# revalarm.net
KiCad netlist of a schematic drawn in EAGLE
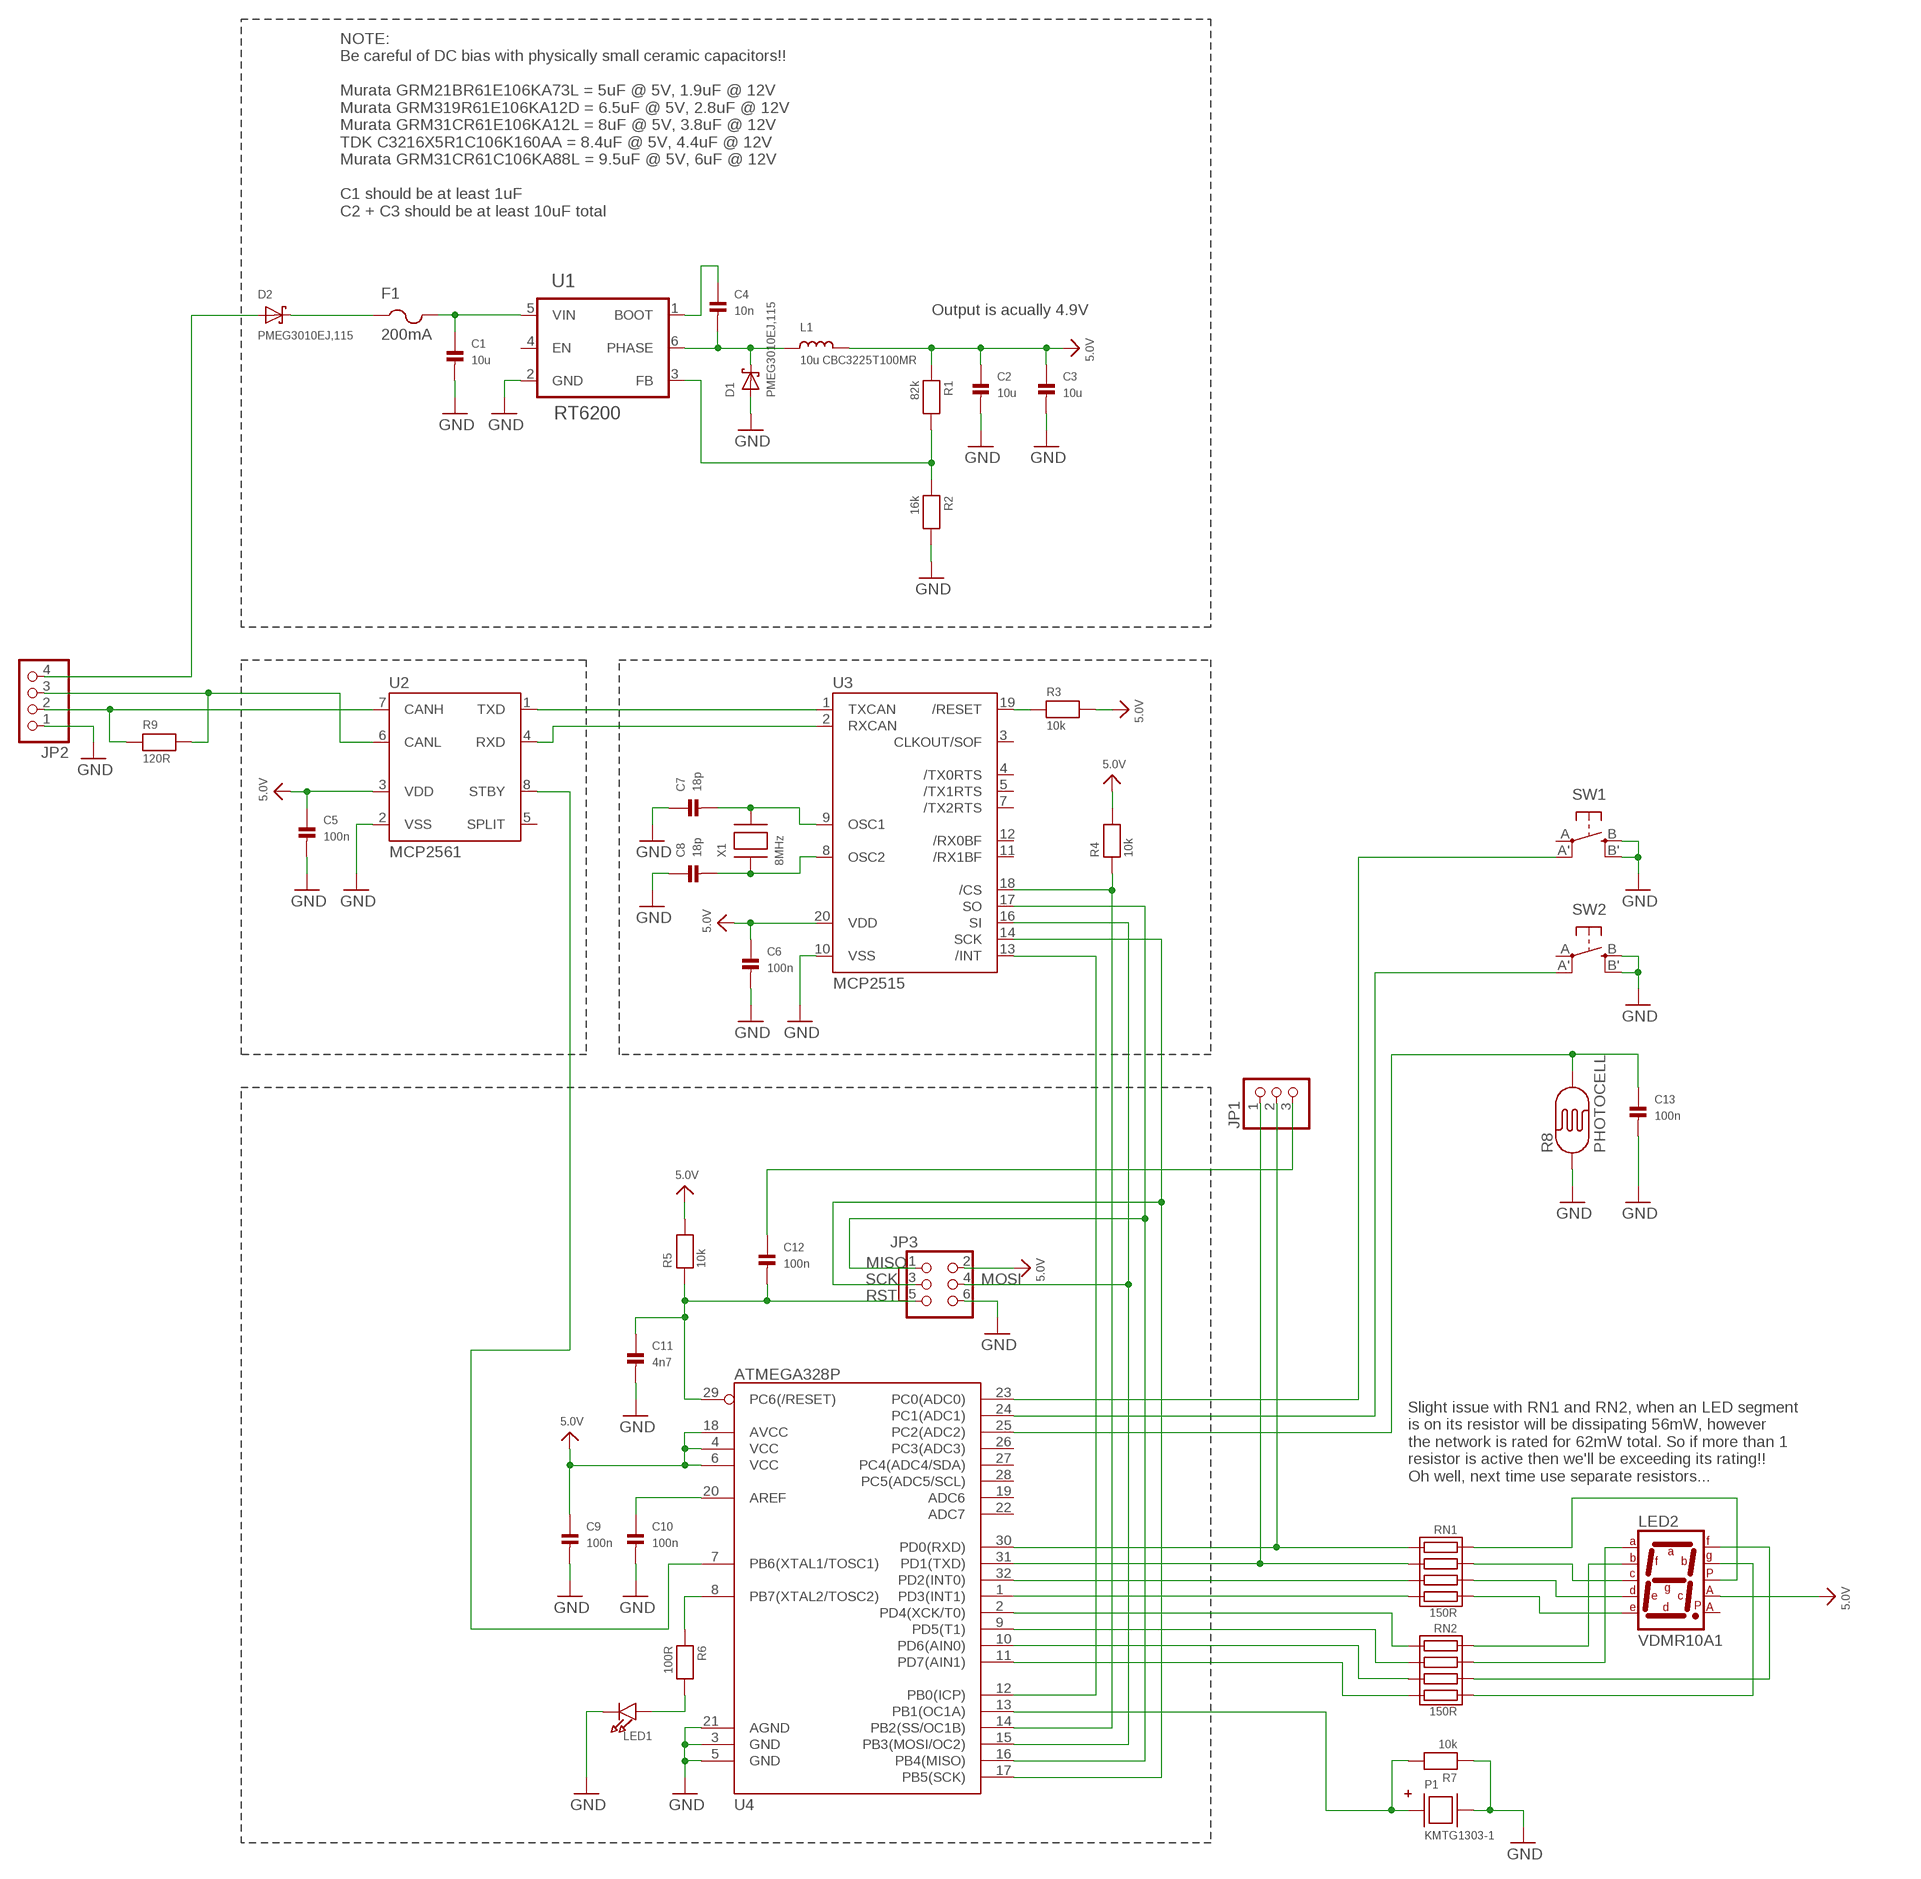
[diagram p0: schematic, sheet 1]

(export (version "E")
  (design (tool "Eeschema 10.0.6"))
  (components
    (comp (ref "C1")
      (value "10u")
      (footprint "eagle-import:1206")
      (libsource (lib "eagle-import") (part "CAP_CERAMIC1206"))
    )
    (comp (ref "C2")
      (value "10u")
      (footprint "eagle-import:1206")
      (libsource (lib "eagle-import") (part "CAP_CERAMIC1206"))
    )
    (comp (ref "C3")
      (value "10u")
      (footprint "eagle-import:1206")
      (libsource (lib "eagle-import") (part "CAP_CERAMIC1206"))
    )
    (comp (ref "C4")
      (value "10n")
      (footprint "eagle-import:0402")
      (libsource (lib "eagle-import") (part "CAP_CERAMIC0402"))
    )
    (comp (ref "C5")
      (value "100n")
      (footprint "eagle-import:0402")
      (libsource (lib "eagle-import") (part "CAP_CERAMIC0402"))
    )
    (comp (ref "C6")
      (value "100n")
      (footprint "eagle-import:0402")
      (libsource (lib "eagle-import") (part "CAP_CERAMIC0402"))
    )
    (comp (ref "C7")
      (value "18p")
      (footprint "eagle-import:0402")
      (libsource (lib "eagle-import") (part "CAP_CERAMIC0402"))
    )
    (comp (ref "C8")
      (value "18p")
      (footprint "eagle-import:0402")
      (libsource (lib "eagle-import") (part "CAP_CERAMIC0402"))
    )
    (comp (ref "C9")
      (value "100n")
      (footprint "eagle-import:0402")
      (libsource (lib "eagle-import") (part "CAP_CERAMIC0402"))
    )
    (comp (ref "C10")
      (value "100n")
      (footprint "eagle-import:0402")
      (libsource (lib "eagle-import") (part "CAP_CERAMIC0402"))
    )
    (comp (ref "C11")
      (value "4n7")
      (footprint "eagle-import:0402")
      (libsource (lib "eagle-import") (part "CAP_CERAMIC0402"))
    )
    (comp (ref "C12")
      (value "100n")
      (footprint "eagle-import:0402")
      (libsource (lib "eagle-import") (part "CAP_CERAMIC0402"))
    )
    (comp (ref "C13")
      (value "100n")
      (footprint "eagle-import:0402")
      (libsource (lib "eagle-import") (part "CAP_CERAMIC0402"))
    )
    (comp (ref "D1")
      (value "PMEG3010EJ,115")
      (footprint "eagle-import:SOD-323")
      (libsource (lib "eagle-import") (part "DIODE-SCHOTTKYSOD-323"))
    )
    (comp (ref "D2")
      (value "PMEG3010EJ,115")
      (footprint "eagle-import:SOD-323")
      (libsource (lib "eagle-import") (part "DIODE-SCHOTTKYSOD-323"))
    )
    (comp (ref "F1")
      (value "200mA")
      (footprint "eagle-import:1206")
      (libsource (lib "eagle-import") (part "PTCFUSE1206"))
    )
    (comp (ref "JP1")
      (value "PINHD-1X3")
      (footprint "eagle-import:1X03")
      (libsource (lib "eagle-import") (part "PINHD-1X3"))
    )
    (comp (ref "JP2")
      (value "PINHD-1X4")
      (footprint "eagle-import:1X04")
      (libsource (lib "eagle-import") (part "PINHD-1X4"))
    )
    (comp (ref "JP3")
      (value "ISP6PINPOGO_PIXELRGB")
      (footprint "eagle-import:POGO60PIN_PIXELRGB")
      (libsource (lib "eagle-import") (part "ISP6PINPOGO_PIXELRGB"))
    )
    (comp (ref "L1")
      (value "10u CBC3225T100MR")
      (footprint "eagle-import:1210K")
      (libsource (lib "eagle-import") (part "INDUCTOR1210K"))
    )
    (comp (ref "LED1")
      (value "LED0805_NOOUTLINE")
      (footprint "eagle-import:CHIPLED_0805_NOOUTLINE")
      (libsource (lib "eagle-import") (part "LED0805_NOOUTLINE"))
    )
    (comp (ref "LED2")
      (value "VDMR10A1")
      (footprint "eagle-import:7SEG-SMD")
      (libsource (lib "eagle-import") (part "7SEGVDMR10A1"))
    )
    (comp (ref "P1")
      (value "KMTG1303-1")
      (footprint "eagle-import:KMTG1303")
      (libsource (lib "eagle-import") (part "PIEZOKMTG1303"))
    )
    (comp (ref "R1")
      (value "82k")
      (footprint "eagle-import:0402")
      (libsource (lib "eagle-import") (part "RESISTOR0402"))
    )
    (comp (ref "R2")
      (value "16k")
      (footprint "eagle-import:0402")
      (libsource (lib "eagle-import") (part "RESISTOR0402"))
    )
    (comp (ref "R3")
      (value "10k")
      (footprint "eagle-import:0402")
      (libsource (lib "eagle-import") (part "RESISTOR0402"))
    )
    (comp (ref "R4")
      (value "10k")
      (footprint "eagle-import:0402")
      (libsource (lib "eagle-import") (part "RESISTOR0402"))
    )
    (comp (ref "R5")
      (value "10k")
      (footprint "eagle-import:0402")
      (libsource (lib "eagle-import") (part "RESISTOR0402"))
    )
    (comp (ref "R6")
      (value "100R")
      (footprint "eagle-import:0402")
      (libsource (lib "eagle-import") (part "RESISTOR0402"))
    )
    (comp (ref "R7")
      (value "10k")
      (footprint "eagle-import:0402")
      (libsource (lib "eagle-import") (part "RESISTOR0402"))
    )
    (comp (ref "R8")
      (value "PHOTOCELL")
      (footprint "eagle-import:PHOTOCELL")
      (libsource (lib "eagle-import") (part "PHOTOCELL"))
    )
    (comp (ref "R9")
      (value "120R")
      (footprint "eagle-import:1206")
      (libsource (lib "eagle-import") (part "RESISTOR1206"))
    )
    (comp (ref "RN1")
      (value "150R")
      (footprint "eagle-import:RESPACK_4X0603")
      (libsource (lib "eagle-import") (part "RESPACK_4STATIC"))
    )
    (comp (ref "RN2")
      (value "150R")
      (footprint "eagle-import:RESPACK_4X0603")
      (libsource (lib "eagle-import") (part "RESPACK_4STATIC"))
    )
    (comp (ref "SW1")
      (value "SPST_TACTMC32882")
      (footprint "eagle-import:TACT_SMD4")
      (libsource (lib "eagle-import") (part "SPST_TACTMC32882"))
    )
    (comp (ref "SW2")
      (value "SPST_TACTMC32882")
      (footprint "eagle-import:TACT_SMD4")
      (libsource (lib "eagle-import") (part "SPST_TACTMC32882"))
    )
    (comp (ref "U1")
      (value "RT6200")
      (footprint "eagle-import:SOT23-6_SM_PAD")
      (libsource (lib "eagle-import") (part "RT6200SOT-23-6"))
    )
    (comp (ref "U2")
      (value "MCP2561")
      (footprint "eagle-import:SOIC8_150MIL_SMPAD")
      (libsource (lib "eagle-import") (part "MCP2561"))
    )
    (comp (ref "U3")
      (value "MCP2515")
      (footprint "eagle-import:TSSOP20")
      (libsource (lib "eagle-import") (part "CANCONTROLLERTSSOP20"))
    )
    (comp (ref "U4")
      (value "ATMEGA328P")
      (footprint "eagle-import:TQFP32-08")
      (libsource (lib "eagle-import") (part "ATMEGA328_SMT"))
    )
    (comp (ref "X1")
      (value "8MHz")
      (footprint "eagle-import:NX5032")
      (libsource (lib "eagle-import") (part "XTALNX5032"))
    )
  )
  (nets
    (net (code "1") (name "/MISO") (class "Default")
      (node (ref "JP3") (pin "1") (pinfunction "1_1") (pintype "passive"))
      (node (ref "U3") (pin "17") (pinfunction "SO_17") (pintype "power_in"))
      (node (ref "U4") (pin "16") (pinfunction "PB4(MISO)_16") (pintype "bidirectional"))
    )
    (net (code "2") (name "/MOSI") (class "Default")
      (node (ref "JP3") (pin "4") (pinfunction "4_4") (pintype "passive"))
      (node (ref "U3") (pin "16") (pinfunction "SI_16") (pintype "passive"))
      (node (ref "U4") (pin "15") (pinfunction "PB3(MOSI/OC2)_15") (pintype "bidirectional"))
    )
    (net (code "3") (name "/RST") (class "Default")
      (node (ref "C11") (pin "1") (pinfunction "P$1_1") (pintype "passive"))
      (node (ref "C12") (pin "2") (pinfunction "P$2_2") (pintype "passive"))
      (node (ref "JP3") (pin "5") (pinfunction "5_5") (pintype "passive"))
      (node (ref "R5") (pin "1") (pinfunction "1_1") (pintype "passive"))
      (node (ref "U4") (pin "29") (pinfunction "PC6(/RESET)_29") (pintype "bidirectional"))
    )
    (net (code "4") (name "/SCK") (class "Default")
      (node (ref "JP3") (pin "3") (pinfunction "3_3") (pintype "passive"))
      (node (ref "U3") (pin "14") (pinfunction "SCK_14") (pintype "passive"))
      (node (ref "U4") (pin "17") (pinfunction "PB5(SCK)_17") (pintype "bidirectional"))
    )
    (net (code "5") (name "5.0V") (class "Default")
      (node (ref "C2") (pin "1") (pinfunction "P$1_1") (pintype "passive"))
      (node (ref "C3") (pin "1") (pinfunction "P$1_1") (pintype "passive"))
      (node (ref "C5") (pin "1") (pinfunction "P$1_1") (pintype "passive"))
      (node (ref "C6") (pin "1") (pinfunction "P$1_1") (pintype "passive"))
      (node (ref "C9") (pin "1") (pinfunction "P$1_1") (pintype "passive"))
      (node (ref "JP3") (pin "2") (pinfunction "2_2") (pintype "power_in"))
      (node (ref "L1") (pin "2") (pinfunction "2_2") (pintype "passive"))
      (node (ref "LED2") (pin "COMM1") (pinfunction "CA1_COMM1") (pintype "passive"))
      (node (ref "R1") (pin "1") (pinfunction "1_1") (pintype "passive"))
      (node (ref "R3") (pin "2") (pinfunction "2_2") (pintype "passive"))
      (node (ref "R4") (pin "2") (pinfunction "2_2") (pintype "passive"))
      (node (ref "R5") (pin "2") (pinfunction "2_2") (pintype "passive"))
      (node (ref "U2") (pin "3") (pinfunction "VDD_3") (pintype "passive"))
      (node (ref "U3") (pin "20") (pinfunction "VDD_20") (pintype "passive"))
      (node (ref "U4") (pin "18") (pinfunction "AVCC_18") (pintype "bidirectional"))
      (node (ref "U4") (pin "4") (pinfunction "VCC_4") (pintype "bidirectional"))
      (node (ref "U4") (pin "6") (pinfunction "VCC_6") (pintype "bidirectional"))
    )
    (net (code "6") (name "GND") (class "Default")
      (node (ref "C1") (pin "2") (pinfunction "P$2_2") (pintype "passive"))
      (node (ref "C10") (pin "2") (pinfunction "P$2_2") (pintype "passive"))
      (node (ref "C11") (pin "2") (pinfunction "P$2_2") (pintype "passive"))
      (node (ref "C13") (pin "2") (pinfunction "P$2_2") (pintype "passive"))
      (node (ref "C2") (pin "2") (pinfunction "P$2_2") (pintype "passive"))
      (node (ref "C3") (pin "2") (pinfunction "P$2_2") (pintype "passive"))
      (node (ref "C5") (pin "2") (pinfunction "P$2_2") (pintype "passive"))
      (node (ref "C6") (pin "2") (pinfunction "P$2_2") (pintype "passive"))
      (node (ref "C7") (pin "1") (pinfunction "P$1_1") (pintype "passive"))
      (node (ref "C8") (pin "1") (pinfunction "P$1_1") (pintype "passive"))
      (node (ref "C9") (pin "2") (pinfunction "P$2_2") (pintype "passive"))
      (node (ref "D1") (pin "A") (pinfunction "A_A") (pintype "passive"))
      (node (ref "JP2") (pin "1") (pinfunction "1_1") (pintype "passive"))
      (node (ref "JP3") (pin "6") (pinfunction "6_6") (pintype "passive"))
      (node (ref "LED1") (pin "C") (pinfunction "C_C") (pintype "passive"))
      (node (ref "P1") (pin "P$2") (pinfunction "GND_P$2") (pintype "passive"))
      (node (ref "R2") (pin "2") (pinfunction "2_2") (pintype "passive"))
      (node (ref "R7") (pin "1") (pinfunction "1_1") (pintype "passive"))
      (node (ref "R8") (pin "1") (pinfunction "P$1_1") (pintype "bidirectional"))
      (node (ref "SW1") (pin "B") (pinfunction "S_B") (pintype "passive"))
      (node (ref "SW1") (pin "B'") (pinfunction "S1_B'") (pintype "passive"))
      (node (ref "SW2") (pin "B") (pinfunction "S_B") (pintype "passive"))
      (node (ref "SW2") (pin "B'") (pinfunction "S1_B'") (pintype "passive"))
      (node (ref "U1") (pin "2") (pinfunction "GND_2") (pintype "passive"))
      (node (ref "U2") (pin "2") (pinfunction "VSS_2") (pintype "passive"))
      (node (ref "U3") (pin "10") (pinfunction "VSS_10") (pintype "passive"))
      (node (ref "U4") (pin "21") (pinfunction "AGND_21") (pintype "bidirectional"))
      (node (ref "U4") (pin "3") (pinfunction "GND_3") (pintype "bidirectional"))
      (node (ref "U4") (pin "5") (pinfunction "GND_5") (pintype "bidirectional"))
    )
    (net (code "7") (name "Net-(C1-P$1)") (class "Default")
      (node (ref "C1") (pin "1") (pinfunction "P$1_1") (pintype "passive"))
      (node (ref "F1") (pin "2") (pinfunction "2_2") (pintype "passive"))
      (node (ref "U1") (pin "5") (pinfunction "VIN_5") (pintype "input"))
    )
    (net (code "8") (name "Net-(C4-P$1)") (class "Default")
      (node (ref "C4") (pin "1") (pinfunction "P$1_1") (pintype "passive"))
      (node (ref "U1") (pin "1") (pinfunction "BOOT_1") (pintype "output"))
    )
    (net (code "9") (name "Net-(C4-P$2)") (class "Default")
      (node (ref "C4") (pin "2") (pinfunction "P$2_2") (pintype "passive"))
      (node (ref "D1") (pin "C") (pinfunction "C_C") (pintype "passive"))
      (node (ref "L1") (pin "1") (pinfunction "1_1") (pintype "passive"))
      (node (ref "U1") (pin "6") (pinfunction "PHASE_6") (pintype "output"))
    )
    (net (code "10") (name "Net-(C7-P$2)") (class "Default")
      (node (ref "C7") (pin "2") (pinfunction "P$2_2") (pintype "passive"))
      (node (ref "U3") (pin "9") (pinfunction "OSC1_9") (pintype "passive"))
      (node (ref "X1") (pin "P$2") (pinfunction "P$2_P$2") (pintype "bidirectional"))
    )
    (net (code "11") (name "Net-(C8-P$2)") (class "Default")
      (node (ref "C8") (pin "2") (pinfunction "P$2_2") (pintype "passive"))
      (node (ref "U3") (pin "8") (pinfunction "OSC2_8") (pintype "passive"))
      (node (ref "X1") (pin "P$1") (pinfunction "P$1_P$1") (pintype "bidirectional"))
    )
    (net (code "12") (name "Net-(C10-P$1)") (class "Default")
      (node (ref "C10") (pin "1") (pinfunction "P$1_1") (pintype "passive"))
      (node (ref "U4") (pin "20") (pinfunction "AREF_20") (pintype "bidirectional"))
    )
    (net (code "13") (name "Net-(C12-P$1)") (class "Default")
      (node (ref "C12") (pin "1") (pinfunction "P$1_1") (pintype "passive"))
      (node (ref "JP1") (pin "3") (pinfunction "3_3") (pintype "passive"))
    )
    (net (code "14") (name "Net-(C13-P$1)") (class "Default")
      (node (ref "C13") (pin "1") (pinfunction "P$1_1") (pintype "passive"))
      (node (ref "R8") (pin "2") (pinfunction "P$2_2") (pintype "bidirectional"))
      (node (ref "U4") (pin "25") (pinfunction "PC2(ADC2)_25") (pintype "bidirectional"))
    )
    (net (code "15") (name "Net-(D2-PadA)") (class "Default")
      (node (ref "D2") (pin "A") (pinfunction "A_A") (pintype "passive"))
      (node (ref "JP2") (pin "4") (pinfunction "4_4") (pintype "passive"))
    )
    (net (code "16") (name "Net-(D2-PadC)") (class "Default")
      (node (ref "D2") (pin "C") (pinfunction "C_C") (pintype "passive"))
      (node (ref "F1") (pin "1") (pinfunction "1_1") (pintype "passive"))
    )
    (net (code "17") (name "Net-(LED1-PadA)") (class "Default")
      (node (ref "LED1") (pin "A") (pinfunction "A_A") (pintype "passive"))
      (node (ref "R6") (pin "2") (pinfunction "2_2") (pintype "passive"))
    )
    (net (code "18") (name "Net-(LED2-PadB)") (class "Default")
      (node (ref "LED2") (pin "B") (pinfunction "B_B") (pintype "passive"))
      (node (ref "RN2") (pin "1") (pinfunction "1_1") (pintype "passive"))
    )
    (net (code "19") (name "Net-(LED2-PadDP)") (class "Default")
      (node (ref "LED2") (pin "DP") (pinfunction "DP_DP") (pintype "passive"))
      (node (ref "RN1") (pin "1") (pinfunction "1_1") (pintype "passive"))
    )
    (net (code "20") (name "Net-(P1-VCC)") (class "Default")
      (node (ref "P1") (pin "P$1") (pinfunction "VCC_P$1") (pintype "passive"))
      (node (ref "R7") (pin "2") (pinfunction "2_2") (pintype "passive"))
      (node (ref "U4") (pin "13") (pinfunction "PB1(OC1A)_13") (pintype "bidirectional"))
    )
    (net (code "21") (name "Net-(RN1-2)") (class "Default")
      (node (ref "JP1") (pin "2") (pinfunction "2_2") (pintype "passive"))
      (node (ref "RN1") (pin "8") (pinfunction "2_8") (pintype "passive"))
      (node (ref "U4") (pin "30") (pinfunction "PD0(RXD)_30") (pintype "bidirectional"))
    )
    (net (code "22") (name "Net-(RN1-3)") (class "Default")
      (node (ref "LED2") (pin "C") (pinfunction "C_C") (pintype "passive"))
      (node (ref "RN1") (pin "2") (pinfunction "3_2") (pintype "passive"))
    )
    (net (code "23") (name "Net-(RN1-4)") (class "Default")
      (node (ref "JP1") (pin "1") (pinfunction "1_1") (pintype "passive"))
      (node (ref "RN1") (pin "7") (pinfunction "4_7") (pintype "passive"))
      (node (ref "U4") (pin "31") (pinfunction "PD1(TXD)_31") (pintype "bidirectional"))
    )
    (net (code "24") (name "Net-(RN1-5)") (class "Default")
      (node (ref "LED2") (pin "D") (pinfunction "D_D") (pintype "passive"))
      (node (ref "RN1") (pin "3") (pinfunction "5_3") (pintype "passive"))
    )
    (net (code "25") (name "Net-(RN1-7)") (class "Default")
      (node (ref "LED2") (pin "E") (pinfunction "E_E") (pintype "passive"))
      (node (ref "RN1") (pin "4") (pinfunction "7_4") (pintype "passive"))
    )
    (net (code "26") (name "Net-(RN1-8)") (class "Default")
      (node (ref "RN1") (pin "5") (pinfunction "8_5") (pintype "passive"))
      (node (ref "U4") (pin "1") (pinfunction "PD3(INT1)_1") (pintype "bidirectional"))
    )
    (net (code "27") (name "Net-(RN2-2)") (class "Default")
      (node (ref "RN2") (pin "8") (pinfunction "2_8") (pintype "passive"))
      (node (ref "U4") (pin "2") (pinfunction "PD4(XCK/T0)_2") (pintype "bidirectional"))
    )
    (net (code "28") (name "Net-(RN2-3)") (class "Default")
      (node (ref "LED2") (pin "A") (pinfunction "A_A") (pintype "passive"))
      (node (ref "RN2") (pin "2") (pinfunction "3_2") (pintype "passive"))
    )
    (net (code "29") (name "Net-(RN2-4)") (class "Default")
      (node (ref "RN2") (pin "7") (pinfunction "4_7") (pintype "passive"))
      (node (ref "U4") (pin "9") (pinfunction "PD5(T1)_9") (pintype "bidirectional"))
    )
    (net (code "30") (name "Net-(RN2-5)") (class "Default")
      (node (ref "LED2") (pin "F") (pinfunction "F_F") (pintype "passive"))
      (node (ref "RN2") (pin "3") (pinfunction "5_3") (pintype "passive"))
    )
    (net (code "31") (name "Net-(RN2-7)") (class "Default")
      (node (ref "LED2") (pin "G") (pinfunction "G_G") (pintype "passive"))
      (node (ref "RN2") (pin "4") (pinfunction "7_4") (pintype "passive"))
    )
    (net (code "32") (name "Net-(RN2-8)") (class "Default")
      (node (ref "RN2") (pin "5") (pinfunction "8_5") (pintype "passive"))
      (node (ref "U4") (pin "11") (pinfunction "PD7(AIN1)_11") (pintype "bidirectional"))
    )
    (net (code "33") (name "Net-(SW1-P1)") (class "Default")
      (node (ref "SW1") (pin "A'") (pinfunction "P1_A'") (pintype "passive"))
      (node (ref "U4") (pin "23") (pinfunction "PC0(ADC0)_23") (pintype "bidirectional"))
    )
    (net (code "34") (name "Net-(SW2-P1)") (class "Default")
      (node (ref "SW2") (pin "A'") (pinfunction "P1_A'") (pintype "passive"))
      (node (ref "U4") (pin "24") (pinfunction "PC1(ADC1)_24") (pintype "bidirectional"))
    )
    (net (code "35") (name "Net-(U1-FB)") (class "Default")
      (node (ref "R1") (pin "2") (pinfunction "2_2") (pintype "passive"))
      (node (ref "R2") (pin "1") (pinfunction "1_1") (pintype "passive"))
      (node (ref "U1") (pin "3") (pinfunction "FB_3") (pintype "power_in"))
    )
    (net (code "36") (name "Net-(U2-CANH)") (class "Default")
      (node (ref "JP2") (pin "2") (pinfunction "2_2") (pintype "passive"))
      (node (ref "R9") (pin "1") (pinfunction "1_1") (pintype "passive"))
      (node (ref "U2") (pin "7") (pinfunction "CANH_7") (pintype "passive"))
    )
    (net (code "37") (name "Net-(U2-CANL)") (class "Default")
      (node (ref "JP2") (pin "3") (pinfunction "3_3") (pintype "passive"))
      (node (ref "R9") (pin "2") (pinfunction "2_2") (pintype "passive"))
      (node (ref "U2") (pin "6") (pinfunction "CANL_6") (pintype "power_in"))
    )
    (net (code "38") (name "Net-(U2-RXD)") (class "Default")
      (node (ref "U2") (pin "4") (pinfunction "RXD_4") (pintype "passive"))
      (node (ref "U3") (pin "2") (pinfunction "RXCAN_2") (pintype "passive"))
    )
    (net (code "39") (name "Net-(U2-STBY)") (class "Default")
      (node (ref "U2") (pin "8") (pinfunction "STBY_8") (pintype "passive"))
      (node (ref "U4") (pin "7") (pinfunction "PB6(XTAL1/TOSC1)_7") (pintype "bidirectional"))
    )
    (net (code "40") (name "Net-(U2-TXD)") (class "Default")
      (node (ref "U2") (pin "1") (pinfunction "TXD_1") (pintype "passive"))
      (node (ref "U3") (pin "1") (pinfunction "TXCAN_1") (pintype "passive"))
    )
    (net (code "41") (name "Net-(U3-{slash}CS)") (class "Default")
      (node (ref "R4") (pin "1") (pinfunction "1_1") (pintype "passive"))
      (node (ref "U3") (pin "18") (pinfunction "/CS_18") (pintype "passive"))
      (node (ref "U4") (pin "14") (pinfunction "PB2(SS/OC1B)_14") (pintype "bidirectional"))
    )
    (net (code "42") (name "Net-(U3-{slash}INT)") (class "Default")
      (node (ref "U3") (pin "13") (pinfunction "/INT_13") (pintype "passive"))
      (node (ref "U4") (pin "12") (pinfunction "PB0(ICP)_12") (pintype "bidirectional"))
    )
    (net (code "43") (name "Net-(U3-{slash}RESET)") (class "Default")
      (node (ref "R3") (pin "1") (pinfunction "1_1") (pintype "passive"))
      (node (ref "U3") (pin "19") (pinfunction "/RESET_19") (pintype "passive"))
    )
    (net (code "44") (name "Net-(U4-PB7(XTAL2{slash}TOSC2))") (class "Default")
      (node (ref "R6") (pin "1") (pinfunction "1_1") (pintype "passive"))
      (node (ref "U4") (pin "8") (pinfunction "PB7(XTAL2/TOSC2)_8") (pintype "bidirectional"))
    )
    (net (code "45") (name "Net-(U4-PD2(INT0))") (class "Default")
      (node (ref "RN1") (pin "6") (pinfunction "6_6") (pintype "passive"))
      (node (ref "U4") (pin "32") (pinfunction "PD2(INT0)_32") (pintype "bidirectional"))
    )
    (net (code "46") (name "Net-(U4-PD6(AIN0))") (class "Default")
      (node (ref "RN2") (pin "6") (pinfunction "6_6") (pintype "passive"))
      (node (ref "U4") (pin "10") (pinfunction "PD6(AIN0)_10") (pintype "bidirectional"))
    )
    (net (code "47") (name "unconnected-(LED2-CA2-PadCOMM2)") (class "Default")
      (node (ref "LED2") (pin "COMM2") (pinfunction "CA2_COMM2") (pintype "passive"))
    )
    (net (code "48") (name "unconnected-(SW1-P-PadA)") (class "Default")
      (node (ref "SW1") (pin "A") (pinfunction "P_A") (pintype "passive"))
    )
    (net (code "49") (name "unconnected-(SW2-P-PadA)") (class "Default")
      (node (ref "SW2") (pin "A") (pinfunction "P_A") (pintype "passive"))
    )
    (net (code "50") (name "unconnected-(U1-EN-Pad4)") (class "Default")
      (node (ref "U1") (pin "4") (pinfunction "EN_4") (pintype "input"))
    )
    (net (code "51") (name "unconnected-(U2-SPLIT-Pad5)") (class "Default")
      (node (ref "U2") (pin "5") (pinfunction "SPLIT_5") (pintype "passive"))
    )
    (net (code "52") (name "unconnected-(U3-CLKOUT{slash}SOF-Pad3)") (class "Default")
      (node (ref "U3") (pin "3") (pinfunction "CLKOUT/SOF_3") (pintype "passive"))
    )
    (net (code "53") (name "unconnected-(U3-{slash}RX0BF-Pad12)") (class "Default")
      (node (ref "U3") (pin "12") (pinfunction "/RX0BF_12") (pintype "passive"))
    )
    (net (code "54") (name "unconnected-(U3-{slash}RX1BF-Pad11)") (class "Default")
      (node (ref "U3") (pin "11") (pinfunction "/RX1BF_11") (pintype "passive"))
    )
    (net (code "55") (name "unconnected-(U3-{slash}TX0RTS-Pad4)") (class "Default")
      (node (ref "U3") (pin "4") (pinfunction "/TX0RTS_4") (pintype "passive"))
    )
    (net (code "56") (name "unconnected-(U3-{slash}TX1RTS-Pad5)") (class "Default")
      (node (ref "U3") (pin "5") (pinfunction "/TX1RTS_5") (pintype "passive"))
    )
    (net (code "57") (name "unconnected-(U3-{slash}TX2RTS-Pad7)") (class "Default")
      (node (ref "U3") (pin "7") (pinfunction "/TX2RTS_7") (pintype "passive"))
    )
    (net (code "58") (name "unconnected-(U4-ADC6-Pad19)") (class "Default")
      (node (ref "U4") (pin "19") (pinfunction "ADC6_19") (pintype "bidirectional"))
    )
    (net (code "59") (name "unconnected-(U4-ADC7-Pad22)") (class "Default")
      (node (ref "U4") (pin "22") (pinfunction "ADC7_22") (pintype "bidirectional"))
    )
    (net (code "60") (name "unconnected-(U4-PC3(ADC3)-Pad26)") (class "Default")
      (node (ref "U4") (pin "26") (pinfunction "PC3(ADC3)_26") (pintype "bidirectional"))
    )
    (net (code "61") (name "unconnected-(U4-PC4(ADC4{slash}SDA)-Pad27)") (class "Default")
      (node (ref "U4") (pin "27") (pinfunction "PC4(ADC4/SDA)_27") (pintype "bidirectional"))
    )
    (net (code "62") (name "unconnected-(U4-PC5(ADC5{slash}SCL)-Pad28)") (class "Default")
      (node (ref "U4") (pin "28") (pinfunction "PC5(ADC5/SCL)_28") (pintype "bidirectional"))
    )
  )
)
